# console.net
KiCad netlist of a schematic drawn in EAGLE
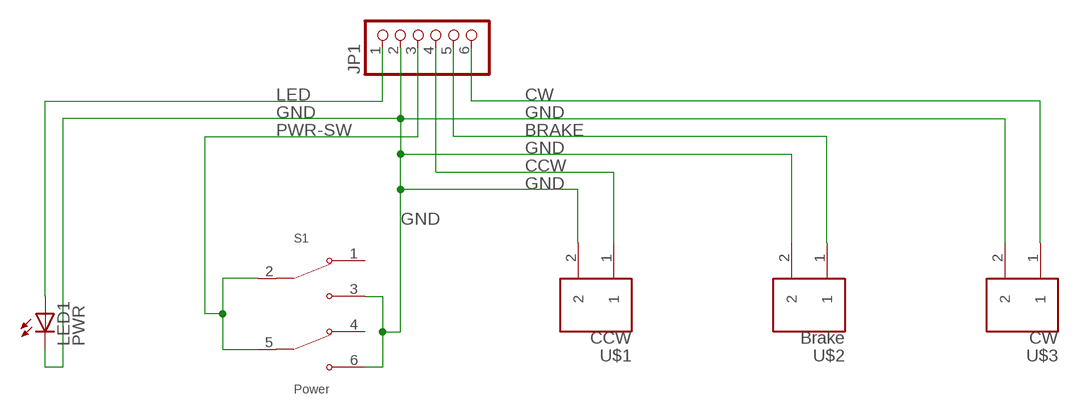
[diagram p0: schematic, sheet 1]

(export (version "E")
  (design (tool "Eeschema 10.0.6"))
  (components
    (comp (ref "JP1")
      (value "PINHD-1X6")
      (footprint "eagle-import:1X06")
      (libsource (lib "eagle-import") (part "PINHD-1X6"))
    )
    (comp (ref "LED1")
      (value "PWR")
      (footprint "eagle-import:CHIPLED_0805")
      (libsource (lib "eagle-import") (part "LEDCHIPLED_0805"))
    )
    (comp (ref "S1")
      (value "Power")
      (footprint "eagle-import:IM211")
      (fields (field (name "MF") "E-Switch") (field (name "MP") "TL2230EEF100"))
      (libsource (lib "eagle-import") (part "IM211"))
    )
    (comp (ref "U$1")
      (value "CCW")
      (footprint "eagle-import:SPST-5MM")
      (libsource (lib "eagle-import") (part "CYT1115-SPST"))
    )
    (comp (ref "U$2")
      (value "Brake")
      (footprint "eagle-import:SPST-5MM")
      (libsource (lib "eagle-import") (part "CYT1115-SPST"))
    )
    (comp (ref "U$3")
      (value "CW")
      (footprint "eagle-import:SPST-5MM")
      (libsource (lib "eagle-import") (part "CYT1115-SPST"))
    )
  )
  (nets
    (net (code "1") (name "/BRAKE") (class "Default")
      (node (ref "JP1") (pin "5") (pinfunction "5_5") (pintype "passive"))
      (node (ref "U$2") (pin "1") (pinfunction "1_1") (pintype "bidirectional"))
    )
    (net (code "2") (name "/CCW") (class "Default")
      (node (ref "JP1") (pin "4") (pinfunction "4_4") (pintype "passive"))
      (node (ref "U$1") (pin "1") (pinfunction "1_1") (pintype "bidirectional"))
    )
    (net (code "3") (name "/CW") (class "Default")
      (node (ref "JP1") (pin "6") (pinfunction "6_6") (pintype "passive"))
      (node (ref "U$3") (pin "1") (pinfunction "1_1") (pintype "bidirectional"))
    )
    (net (code "4") (name "/GND") (class "Default")
      (node (ref "JP1") (pin "2") (pinfunction "2_2") (pintype "passive"))
      (node (ref "LED1") (pin "C") (pinfunction "C_C") (pintype "passive"))
      (node (ref "S1") (pin "3") (pinfunction "NO1_3") (pintype "passive"))
      (node (ref "S1") (pin "6") (pinfunction "NO2_6") (pintype "passive"))
      (node (ref "U$1") (pin "2") (pinfunction "2_2") (pintype "bidirectional"))
      (node (ref "U$2") (pin "2") (pinfunction "2_2") (pintype "bidirectional"))
      (node (ref "U$3") (pin "2") (pinfunction "2_2") (pintype "bidirectional"))
    )
    (net (code "5") (name "/LED") (class "Default")
      (node (ref "JP1") (pin "1") (pinfunction "1_1") (pintype "passive"))
      (node (ref "LED1") (pin "A") (pinfunction "A_A") (pintype "passive"))
    )
    (net (code "6") (name "/PWR-SW") (class "Default")
      (node (ref "JP1") (pin "3") (pinfunction "3_3") (pintype "passive"))
      (node (ref "S1") (pin "2") (pinfunction "COM1_2") (pintype "passive"))
      (node (ref "S1") (pin "5") (pinfunction "COM2_5") (pintype "passive"))
    )
    (net (code "7") (name "unconnected-(S1-NC1-Pad1)") (class "Default")
      (node (ref "S1") (pin "1") (pinfunction "NC1_1") (pintype "passive"))
    )
    (net (code "8") (name "unconnected-(S1-NC2-Pad4)") (class "Default")
      (node (ref "S1") (pin "4") (pinfunction "NC2_4") (pintype "passive"))
    )
  )
)
